# alte_schaltung_nicer.net
KiCad netlist of a schematic drawn in EAGLE
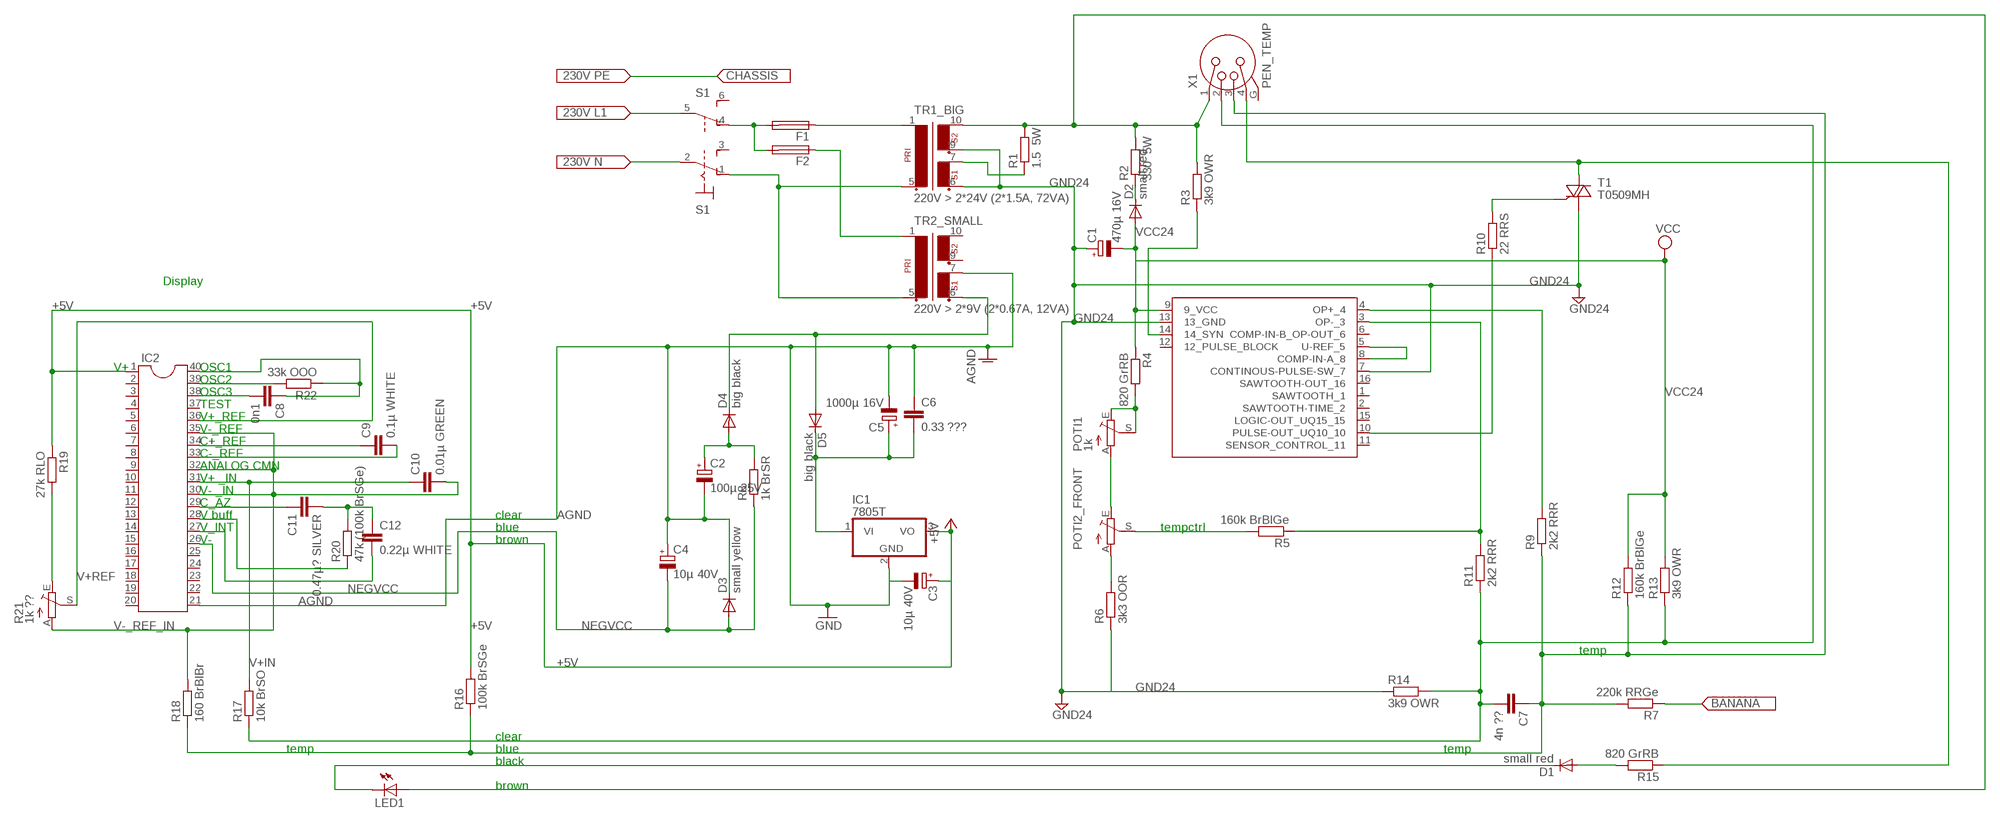
[diagram p0: schematic, sheet 1]

(export (version "E")
  (design (tool "Eeschema 10.0.6"))
  (components
    (comp (ref "C1")
      (value "470µ 16V")
      (footprint "eagle-import:E5-10,5")
      (libsource (lib "eagle-import") (part "CPOL-EUE5-10.5"))
    )
    (comp (ref "C2")
      (value "100µ 25V")
      (footprint "eagle-import:E5-10,5")
      (libsource (lib "eagle-import") (part "CPOL-EUE5-10.5"))
    )
    (comp (ref "C3")
      (value "10µ 40V")
      (footprint "eagle-import:E5-10,5")
      (libsource (lib "eagle-import") (part "CPOL-EUE5-10.5"))
    )
    (comp (ref "C4")
      (value "10µ 40V")
      (footprint "eagle-import:E5-10,5")
      (libsource (lib "eagle-import") (part "CPOL-EUE5-10.5"))
    )
    (comp (ref "C5")
      (value "1000µ 16V")
      (footprint "eagle-import:E5-10,5")
      (libsource (lib "eagle-import") (part "CPOL-EUE5-10.5"))
    )
    (comp (ref "C6")
      (value "0.33 ???")
      (footprint "eagle-import:C075-042X103")
      (libsource (lib "eagle-import") (part "C-EU075-042X103"))
    )
    (comp (ref "C7")
      (value "4n ??")
      (footprint "eagle-import:C050-024X044")
      (libsource (lib "eagle-import") (part "C-EU050-024X044"))
    )
    (comp (ref "C8")
      (value "0n1")
      (footprint "eagle-import:C050-024X044")
      (libsource (lib "eagle-import") (part "C-EU050-024X044"))
    )
    (comp (ref "C9")
      (value "0.1µ WHITE")
      (footprint "eagle-import:C102-043X133")
      (libsource (lib "eagle-import") (part "C-EU102-043X133"))
    )
    (comp (ref "C10")
      (value "0.01µ GREEN")
      (footprint "eagle-import:C102-043X133")
      (libsource (lib "eagle-import") (part "C-EU102-043X133"))
    )
    (comp (ref "C11")
      (value "0.47µ? SILVER")
      (footprint "eagle-import:C102-043X133")
      (libsource (lib "eagle-import") (part "C-EU102-043X133"))
    )
    (comp (ref "C12")
      (value "0.22µ WHITE")
      (footprint "eagle-import:C102-043X133")
      (libsource (lib "eagle-import") (part "C-EU102-043X133"))
    )
    (comp (ref "D1")
      (value "small red")
      (footprint "eagle-import:DO41-10")
      (libsource (lib "eagle-import") (part "1N4004"))
    )
    (comp (ref "D2")
      (value "small red")
      (footprint "eagle-import:DO41-10")
      (libsource (lib "eagle-import") (part "1N4004"))
    )
    (comp (ref "D3")
      (value "small yellow")
      (footprint "eagle-import:DO35-10")
      (libsource (lib "eagle-import") (part "1N4446"))
    )
    (comp (ref "D4")
      (value "big black")
      (footprint "eagle-import:DO41-10")
      (libsource (lib "eagle-import") (part "1N4942"))
    )
    (comp (ref "D5")
      (value "big black")
      (footprint "eagle-import:DO41-10")
      (libsource (lib "eagle-import") (part "1N4942"))
    )
    (comp (ref "F1")
      (value "SH25")
      (footprint "eagle-import:SH25")
      (fields (field (name "MF") "SCHURTER") (field (name "MPN") "0031.8211"))
      (libsource (lib "eagle-import") (part "SH25"))
    )
    (comp (ref "F2")
      (value "SH25")
      (footprint "eagle-import:SH25")
      (fields (field (name "MF") "SCHURTER") (field (name "MPN") "0031.8211"))
      (libsource (lib "eagle-import") (part "SH25"))
    )
    (comp (ref "IC1")
      (value "7805T")
      (footprint "eagle-import:TO220H")
      (libsource (lib "eagle-import") (part "78T05"))
    )
    (comp (ref "IC2")
      (value "DIL40")
      (footprint "eagle-import:DIL40")
      (libsource (lib "eagle-import") (part "DIL40"))
    )
    (comp (ref "LED1")
      (value "LED3MM")
      (footprint "eagle-import:LED3MM")
      (libsource (lib "eagle-import") (part "LED3MM"))
    )
    (comp (ref "POTI1")
      (value "1k")
      (footprint "eagle-import:LI10")
      (libsource (lib "eagle-import") (part "TRIM_EU-LI10"))
    )
    (comp (ref "POTI2_FRONT")
      (value "TRIM_EU-RJ9W")
      (footprint "eagle-import:RJ9W")
      (libsource (lib "eagle-import") (part "TRIM_EU-RJ9W"))
    )
    (comp (ref "R1")
      (value "1.5 5W")
      (footprint "eagle-import:0922_22")
      (libsource (lib "eagle-import") (part "R-EU_0922/22"))
    )
    (comp (ref "R2")
      (value "330 5W")
      (footprint "eagle-import:0922_22")
      (libsource (lib "eagle-import") (part "R-EU_0922/22"))
    )
    (comp (ref "R3")
      (value "3k9 OWR")
      (footprint "eagle-import:0207_12")
      (libsource (lib "eagle-import") (part "R-EU_0207/12"))
    )
    (comp (ref "R4")
      (value "820 GrRB")
      (footprint "eagle-import:0207_12")
      (libsource (lib "eagle-import") (part "R-EU_0207/12"))
    )
    (comp (ref "R5")
      (value "160k BrBlGe")
      (footprint "eagle-import:0207_12")
      (libsource (lib "eagle-import") (part "R-EU_0207/12"))
    )
    (comp (ref "R6")
      (value "3k3 OOR")
      (footprint "eagle-import:0207_12")
      (libsource (lib "eagle-import") (part "R-EU_0207/12"))
    )
    (comp (ref "R7")
      (value "220k RRGe")
      (footprint "eagle-import:0207_12")
      (libsource (lib "eagle-import") (part "R-EU_0207/12"))
    )
    (comp (ref "R8")
      (value "1k BrSR")
      (footprint "eagle-import:0207_12")
      (libsource (lib "eagle-import") (part "R-EU_0207/12"))
    )
    (comp (ref "R9")
      (value "2k2 RRR")
      (footprint "eagle-import:0207_12")
      (libsource (lib "eagle-import") (part "R-EU_0207/12"))
    )
    (comp (ref "R10")
      (value "22 RRS")
      (footprint "eagle-import:0207_12")
      (libsource (lib "eagle-import") (part "R-EU_0207/12"))
    )
    (comp (ref "R11")
      (value "2k2 RRR")
      (footprint "eagle-import:0207_12")
      (libsource (lib "eagle-import") (part "R-EU_0207/12"))
    )
    (comp (ref "R12")
      (value "160k BrBlGe")
      (footprint "eagle-import:0207_12")
      (libsource (lib "eagle-import") (part "R-EU_0207/12"))
    )
    (comp (ref "R13")
      (value "3k9 OWR")
      (footprint "eagle-import:0207_12")
      (libsource (lib "eagle-import") (part "R-EU_0207/12"))
    )
    (comp (ref "R14")
      (value "3k9 OWR")
      (footprint "eagle-import:0207_12")
      (libsource (lib "eagle-import") (part "R-EU_0207/12"))
    )
    (comp (ref "R15")
      (value "820 GrRB")
      (footprint "eagle-import:0207_12")
      (libsource (lib "eagle-import") (part "R-EU_0207/12"))
    )
    (comp (ref "R16")
      (value "100k BrSGe")
      (footprint "eagle-import:0207_12")
      (libsource (lib "eagle-import") (part "R-EU_0207/12"))
    )
    (comp (ref "R17")
      (value "10k BrSO")
      (footprint "eagle-import:0207_12")
      (libsource (lib "eagle-import") (part "R-EU_0207/12"))
    )
    (comp (ref "R18")
      (value "160 BrBlBr")
      (footprint "eagle-import:0207_12")
      (libsource (lib "eagle-import") (part "R-EU_0207/12"))
    )
    (comp (ref "R19")
      (value "27k RLO")
      (footprint "eagle-import:0207_12")
      (libsource (lib "eagle-import") (part "R-EU_0207/12"))
    )
    (comp (ref "R20")
      (value "47k (100k BrSGe)")
      (footprint "eagle-import:0207_12")
      (libsource (lib "eagle-import") (part "R-EU_0207/12"))
    )
    (comp (ref "R21")
      (value "1k ??")
      (footprint "eagle-import:SP19L")
      (libsource (lib "eagle-import") (part "TRIM_EU-B90P"))
    )
    (comp (ref "R22")
      (value "33k OOO")
      (footprint "eagle-import:0207_12")
      (libsource (lib "eagle-import") (part "R-EU_0207/12"))
    )
    (comp (ref "S1")
      (value "320-938")
      (footprint "eagle-import:320-938")
      (libsource (lib "eagle-import") (part "320-938"))
    )
    (comp (ref "T1")
      (value "T0509MH")
      (footprint "eagle-import:TO220AB")
      (libsource (lib "eagle-import") (part "BT136"))
    )
    (comp (ref "TR1_BIG")
      (value "220V > 2*24V (2*1.5A, 72VA)")
      (footprint "eagle-import:EI42-2")
      (libsource (lib "eagle-import") (part "EI42-2"))
    )
    (comp (ref "TR2_SMALL")
      (value "220V > 2*9V (2*0.67A, 12VA)")
      (footprint "eagle-import:EI42-2")
      (libsource (lib "eagle-import") (part "EI42-2"))
    )
    (comp (ref "U$1")
      (value "U106BS-DIL16")
      (footprint "eagle-import:DIL16")
      (libsource (lib "eagle-import") (part "U106BS-DIL16"))
    )
    (comp (ref "X1")
      (value "PEN_TEMP")
      (footprint "eagle-import:NC4FBV")
      (fields (field (name "MPN") "NC4FBV"))
      (libsource (lib "eagle-import") (part "NC4FBV"))
    )
  )
  (nets
    (net (code "1") (name "+5V") (class "Default")
      (node (ref "C3") (pin "+") (pinfunction "+_+") (pintype "passive"))
      (node (ref "IC1") (pin "3") (pinfunction "VO_3") (pintype "passive"))
      (node (ref "IC2") (pin "1") (pinfunction "1_1") (pintype "passive"))
      (node (ref "R16") (pin "2") (pinfunction "2_2") (pintype "passive"))
      (node (ref "R19") (pin "1") (pinfunction "1_1") (pintype "passive"))
    )
    (net (code "2") (name "/NEGVCC") (class "Default")
      (node (ref "C4") (pin "-") (pinfunction "-_-") (pintype "passive"))
      (node (ref "D3") (pin "A") (pinfunction "A_A") (pintype "passive"))
      (node (ref "IC2") (pin "26") (pinfunction "26_26") (pintype "passive"))
      (node (ref "R8") (pin "1") (pinfunction "1_1") (pintype "passive"))
    )
    (net (code "3") (name "/V+IN") (class "Default")
      (node (ref "C10") (pin "1") (pinfunction "1_1") (pintype "passive"))
      (node (ref "IC2") (pin "31") (pinfunction "31_31") (pintype "passive"))
      (node (ref "R17") (pin "2") (pinfunction "2_2") (pintype "passive"))
    )
    (net (code "4") (name "/V+REF") (class "Default")
      (node (ref "IC2") (pin "36") (pinfunction "36_36") (pintype "passive"))
      (node (ref "R21") (pin "S") (pinfunction "S_S") (pintype "passive"))
    )
    (net (code "5") (name "/V-_REF_IN") (class "Default")
      (node (ref "C10") (pin "2") (pinfunction "2_2") (pintype "passive"))
      (node (ref "IC2") (pin "30") (pinfunction "30_30") (pintype "passive"))
      (node (ref "IC2") (pin "32") (pinfunction "32_32") (pintype "passive"))
      (node (ref "IC2") (pin "35") (pinfunction "35_35") (pintype "passive"))
      (node (ref "R18") (pin "2") (pinfunction "2_2") (pintype "passive"))
      (node (ref "R21") (pin "A") (pinfunction "A_A") (pintype "passive"))
    )
    (net (code "6") (name "AGND") (class "Default")
      (node (ref "C2") (pin "-") (pinfunction "-_-") (pintype "passive"))
      (node (ref "C3") (pin "-") (pinfunction "-_-") (pintype "passive"))
      (node (ref "C4") (pin "+") (pinfunction "+_+") (pintype "passive"))
      (node (ref "C5") (pin "-") (pinfunction "-_-") (pintype "passive"))
      (node (ref "C6") (pin "1") (pinfunction "1_1") (pintype "passive"))
      (node (ref "D3") (pin "C") (pinfunction "C_C") (pintype "passive"))
      (node (ref "IC1") (pin "2") (pinfunction "GND_2") (pintype "passive"))
      (node (ref "IC2") (pin "21") (pinfunction "21_21") (pintype "passive"))
      (node (ref "TR2_SMALL") (pin "7") (pinfunction "4_7") (pintype "passive"))
    )
    (net (code "7") (name "GND24") (class "Default")
      (node (ref "C1") (pin "+") (pinfunction "+_+") (pintype "passive"))
      (node (ref "R14") (pin "1") (pinfunction "1_1") (pintype "passive"))
      (node (ref "R6") (pin "1") (pinfunction "1_1") (pintype "passive"))
      (node (ref "T1") (pin "1") (pinfunction "A1_1") (pintype "passive"))
      (node (ref "TR1_BIG") (pin "6") (pinfunction "3_6") (pintype "passive"))
      (node (ref "TR1_BIG") (pin "9") (pinfunction "5_9") (pintype "passive"))
      (node (ref "U$1") (pin "13") (pinfunction "13_GND_13") (pintype "power_in"))
      (node (ref "U$1") (pin "7") (pinfunction "CONTINOUS-PULSE-SW_7_7") (pintype "input"))
    )
    (net (code "8") (name "Net-(C2-Pad+)") (class "Default")
      (node (ref "C2") (pin "+") (pinfunction "+_+") (pintype "passive"))
      (node (ref "D4") (pin "A") (pinfunction "A_A") (pintype "passive"))
      (node (ref "R8") (pin "2") (pinfunction "2_2") (pintype "passive"))
    )
    (net (code "9") (name "Net-(C7-Pad1)") (class "Default")
      (node (ref "C7") (pin "1") (pinfunction "1_1") (pintype "passive"))
      (node (ref "R12") (pin "1") (pinfunction "1_1") (pintype "passive"))
      (node (ref "R16") (pin "1") (pinfunction "1_1") (pintype "passive"))
      (node (ref "R18") (pin "1") (pinfunction "1_1") (pintype "passive"))
      (node (ref "R7") (pin "2") (pinfunction "2_2") (pintype "passive"))
      (node (ref "R9") (pin "1") (pinfunction "1_1") (pintype "passive"))
      (node (ref "X1") (pin "3") (pinfunction "3_3") (pintype "passive"))
    )
    (net (code "10") (name "Net-(C7-Pad2)") (class "Default")
      (node (ref "C7") (pin "2") (pinfunction "2_2") (pintype "passive"))
      (node (ref "R11") (pin "1") (pinfunction "1_1") (pintype "passive"))
      (node (ref "R13") (pin "1") (pinfunction "1_1") (pintype "passive"))
      (node (ref "R14") (pin "2") (pinfunction "2_2") (pintype "passive"))
      (node (ref "R17") (pin "1") (pinfunction "1_1") (pintype "passive"))
      (node (ref "X1") (pin "2") (pinfunction "2_2") (pintype "passive"))
    )
    (net (code "11") (name "Net-(C8-Pad1)") (class "Default")
      (node (ref "C8") (pin "1") (pinfunction "1_1") (pintype "passive"))
      (node (ref "IC2") (pin "40") (pinfunction "40_40") (pintype "passive"))
      (node (ref "R22") (pin "1") (pinfunction "1_1") (pintype "passive"))
    )
    (net (code "12") (name "Net-(C8-Pad2)") (class "Default")
      (node (ref "C8") (pin "2") (pinfunction "2_2") (pintype "passive"))
      (node (ref "IC2") (pin "38") (pinfunction "38_38") (pintype "passive"))
    )
    (net (code "13") (name "Net-(C9-Pad1)") (class "Default")
      (node (ref "C9") (pin "1") (pinfunction "1_1") (pintype "passive"))
      (node (ref "IC2") (pin "34") (pinfunction "34_34") (pintype "passive"))
    )
    (net (code "14") (name "Net-(C9-Pad2)") (class "Default")
      (node (ref "C9") (pin "2") (pinfunction "2_2") (pintype "passive"))
      (node (ref "IC2") (pin "33") (pinfunction "33_33") (pintype "passive"))
    )
    (net (code "15") (name "Net-(C11-Pad1)") (class "Default")
      (node (ref "C11") (pin "1") (pinfunction "1_1") (pintype "passive"))
      (node (ref "IC2") (pin "29") (pinfunction "29_29") (pintype "passive"))
    )
    (net (code "16") (name "Net-(C11-Pad2)") (class "Default")
      (node (ref "C11") (pin "2") (pinfunction "2_2") (pintype "passive"))
      (node (ref "C12") (pin "1") (pinfunction "1_1") (pintype "passive"))
      (node (ref "R20") (pin "2") (pinfunction "2_2") (pintype "passive"))
    )
    (net (code "17") (name "Net-(C12-Pad2)") (class "Default")
      (node (ref "C12") (pin "2") (pinfunction "2_2") (pintype "passive"))
      (node (ref "IC2") (pin "27") (pinfunction "27_27") (pintype "passive"))
    )
    (net (code "18") (name "Net-(D1-PadA)") (class "Default")
      (node (ref "D1") (pin "A") (pinfunction "A_A") (pintype "passive"))
      (node (ref "R15") (pin "2") (pinfunction "2_2") (pintype "passive"))
    )
    (net (code "19") (name "Net-(D2-PadC)") (class "Default")
      (node (ref "D2") (pin "C") (pinfunction "C_C") (pintype "passive"))
      (node (ref "R2") (pin "1") (pinfunction "1_1") (pintype "passive"))
    )
    (net (code "20") (name "Net-(F1-Pad1)") (class "Default")
      (node (ref "F1") (pin "1") (pinfunction "1_1") (pintype "passive"))
      (node (ref "TR1_BIG") (pin "1") (pinfunction "1_1") (pintype "passive"))
    )
    (net (code "21") (name "Net-(F2-Pad1)") (class "Default")
      (node (ref "F2") (pin "1") (pinfunction "1_1") (pintype "passive"))
      (node (ref "TR2_SMALL") (pin "1") (pinfunction "1_1") (pintype "passive"))
    )
    (net (code "22") (name "Net-(IC1-VI)") (class "Default")
      (node (ref "C5") (pin "+") (pinfunction "+_+") (pintype "passive"))
      (node (ref "C6") (pin "2") (pinfunction "2_2") (pintype "passive"))
      (node (ref "D5") (pin "C") (pinfunction "C_C") (pintype "passive"))
      (node (ref "IC1") (pin "1") (pinfunction "VI_1") (pintype "input"))
    )
    (net (code "23") (name "Net-(IC2-Pad28)") (class "Default")
      (node (ref "IC2") (pin "28") (pinfunction "28_28") (pintype "passive"))
      (node (ref "R20") (pin "1") (pinfunction "1_1") (pintype "passive"))
    )
    (net (code "24") (name "Net-(IC2-Pad39)") (class "Default")
      (node (ref "IC2") (pin "39") (pinfunction "39_39") (pintype "passive"))
      (node (ref "R22") (pin "2") (pinfunction "2_2") (pintype "passive"))
    )
    (net (code "25") (name "Net-(LED1-C)") (class "Default")
      (node (ref "D1") (pin "C") (pinfunction "C_C") (pintype "passive"))
      (node (ref "LED1") (pin "K") (pinfunction "C_K") (pintype "passive"))
    )
    (net (code "26") (name "Net-(POTI1-PadA)") (class "Default")
      (node (ref "POTI1") (pin "A") (pinfunction "A_A") (pintype "passive"))
      (node (ref "POTI2_FRONT") (pin "E") (pinfunction "E_E") (pintype "passive"))
    )
    (net (code "27") (name "Net-(POTI1-PadE)") (class "Default")
      (node (ref "POTI1") (pin "E") (pinfunction "E_E") (pintype "passive"))
      (node (ref "POTI1") (pin "S") (pinfunction "S_S") (pintype "passive"))
      (node (ref "R4") (pin "2") (pinfunction "2_2") (pintype "passive"))
    )
    (net (code "28") (name "Net-(POTI2_FRONT-PadA)") (class "Default")
      (node (ref "POTI2_FRONT") (pin "A") (pinfunction "A_A") (pintype "passive"))
      (node (ref "R6") (pin "2") (pinfunction "2_2") (pintype "passive"))
    )
    (net (code "29") (name "Net-(POTI2_FRONT-PadS)") (class "Default")
      (node (ref "POTI2_FRONT") (pin "S") (pinfunction "S_S") (pintype "passive"))
      (node (ref "R5") (pin "2") (pinfunction "2_2") (pintype "passive"))
    )
    (net (code "30") (name "Net-(R19-Pad2)") (class "Default")
      (node (ref "R19") (pin "2") (pinfunction "2_2") (pintype "passive"))
      (node (ref "R21") (pin "E") (pinfunction "E_E") (pintype "passive"))
    )
    (net (code "31") (name "Net-(S1A-O)") (class "Default")
      (node (ref "S1") (pin "1") (pinfunction "O_1") (pintype "passive"))
      (node (ref "TR1_BIG") (pin "5") (pinfunction "2_5") (pintype "passive"))
      (node (ref "TR2_SMALL") (pin "5") (pinfunction "2_5") (pintype "passive"))
    )
    (net (code "32") (name "Net-(S1B-O)") (class "Default")
      (node (ref "F1") (pin "2") (pinfunction "2_2") (pintype "passive"))
      (node (ref "F2") (pin "2") (pinfunction "2_2") (pintype "passive"))
      (node (ref "S1") (pin "4") (pinfunction "O_4") (pintype "passive"))
    )
    (net (code "33") (name "Net-(T1-A2)") (class "Default")
      (node (ref "R15") (pin "1") (pinfunction "1_1") (pintype "passive"))
      (node (ref "T1") (pin "2") (pinfunction "A2_2") (pintype "passive"))
      (node (ref "X1") (pin "4") (pinfunction "4_4") (pintype "passive"))
    )
    (net (code "34") (name "Net-(T1-G)") (class "Default")
      (node (ref "R10") (pin "2") (pinfunction "2_2") (pintype "passive"))
      (node (ref "T1") (pin "3") (pinfunction "G_3") (pintype "passive"))
    )
    (net (code "35") (name "Net-(TR1_BIG-4)") (class "Default")
      (node (ref "R1") (pin "1") (pinfunction "1_1") (pintype "passive"))
      (node (ref "TR1_BIG") (pin "7") (pinfunction "4_7") (pintype "passive"))
    )
    (net (code "36") (name "Net-(TR1_BIG-6)") (class "Default")
      (node (ref "LED1") (pin "A") (pinfunction "A_A") (pintype "passive"))
      (node (ref "R1") (pin "2") (pinfunction "2_2") (pintype "passive"))
      (node (ref "R2") (pin "2") (pinfunction "2_2") (pintype "passive"))
      (node (ref "R3") (pin "2") (pinfunction "2_2") (pintype "passive"))
      (node (ref "TR1_BIG") (pin "10") (pinfunction "6_10") (pintype "passive"))
      (node (ref "X1") (pin "1") (pinfunction "1_1") (pintype "passive"))
    )
    (net (code "37") (name "Net-(TR2_SMALL-3)") (class "Default")
      (node (ref "D4") (pin "C") (pinfunction "C_C") (pintype "passive"))
      (node (ref "D5") (pin "A") (pinfunction "A_A") (pintype "passive"))
      (node (ref "TR2_SMALL") (pin "6") (pinfunction "3_6") (pintype "passive"))
    )
    (net (code "38") (name "Net-(U$1-14_SYN)") (class "Default")
      (node (ref "R3") (pin "1") (pinfunction "1_1") (pintype "passive"))
      (node (ref "U$1") (pin "14") (pinfunction "14_SYN_14") (pintype "input"))
    )
    (net (code "39") (name "Net-(U$1-COMP-IN-A_8)") (class "Default")
      (node (ref "U$1") (pin "5") (pinfunction "U-REF_5_5") (pintype "input"))
      (node (ref "U$1") (pin "8") (pinfunction "COMP-IN-A_8_8") (pintype "input"))
    )
    (net (code "40") (name "Net-(U$1-OP+_4)") (class "Default")
      (node (ref "R9") (pin "2") (pinfunction "2_2") (pintype "passive"))
      (node (ref "U$1") (pin "4") (pinfunction "OP+_4_4") (pintype "input"))
    )
    (net (code "41") (name "Net-(U$1-OP-_3)") (class "Default")
      (node (ref "R11") (pin "2") (pinfunction "2_2") (pintype "passive"))
      (node (ref "R5") (pin "1") (pinfunction "1_1") (pintype "passive"))
      (node (ref "U$1") (pin "3") (pinfunction "OP-_3_3") (pintype "input"))
    )
    (net (code "42") (name "Net-(U$1-PULSE-OUT_UQ10_10)") (class "Default")
      (node (ref "R10") (pin "1") (pinfunction "1_1") (pintype "passive"))
      (node (ref "U$1") (pin "10") (pinfunction "PULSE-OUT_UQ10_10_10") (pintype "output"))
    )
    (net (code "43") (name "VCC") (class "Default")
      (node (ref "C1") (pin "-") (pinfunction "-_-") (pintype "passive"))
      (node (ref "D2") (pin "A") (pinfunction "A_A") (pintype "passive"))
      (node (ref "R12") (pin "2") (pinfunction "2_2") (pintype "passive"))
      (node (ref "R13") (pin "2") (pinfunction "2_2") (pintype "passive"))
      (node (ref "R4") (pin "1") (pinfunction "1_1") (pintype "passive"))
      (node (ref "U$1") (pin "9") (pinfunction "9_VCC_9") (pintype "power_in"))
    )
    (net (code "44") (name "unconnected-(IC2-Pad2)") (class "Default")
      (node (ref "IC2") (pin "2") (pinfunction "2_2") (pintype "passive"))
    )
    (net (code "45") (name "unconnected-(IC2-Pad3)") (class "Default")
      (node (ref "IC2") (pin "3") (pinfunction "3_3") (pintype "passive"))
    )
    (net (code "46") (name "unconnected-(IC2-Pad4)") (class "Default")
      (node (ref "IC2") (pin "4") (pinfunction "4_4") (pintype "passive"))
    )
    (net (code "47") (name "unconnected-(IC2-Pad5)") (class "Default")
      (node (ref "IC2") (pin "5") (pinfunction "5_5") (pintype "passive"))
    )
    (net (code "48") (name "unconnected-(IC2-Pad6)") (class "Default")
      (node (ref "IC2") (pin "6") (pinfunction "6_6") (pintype "passive"))
    )
    (net (code "49") (name "unconnected-(IC2-Pad7)") (class "Default")
      (node (ref "IC2") (pin "7") (pinfunction "7_7") (pintype "passive"))
    )
    (net (code "50") (name "unconnected-(IC2-Pad8)") (class "Default")
      (node (ref "IC2") (pin "8") (pinfunction "8_8") (pintype "passive"))
    )
    (net (code "51") (name "unconnected-(IC2-Pad9)") (class "Default")
      (node (ref "IC2") (pin "9") (pinfunction "9_9") (pintype "passive"))
    )
    (net (code "52") (name "unconnected-(IC2-Pad10)") (class "Default")
      (node (ref "IC2") (pin "10") (pinfunction "10_10") (pintype "passive"))
    )
    (net (code "53") (name "unconnected-(IC2-Pad11)") (class "Default")
      (node (ref "IC2") (pin "11") (pinfunction "11_11") (pintype "passive"))
    )
    (net (code "54") (name "unconnected-(IC2-Pad12)") (class "Default")
      (node (ref "IC2") (pin "12") (pinfunction "12_12") (pintype "passive"))
    )
    (net (code "55") (name "unconnected-(IC2-Pad13)") (class "Default")
      (node (ref "IC2") (pin "13") (pinfunction "13_13") (pintype "passive"))
    )
    (net (code "56") (name "unconnected-(IC2-Pad14)") (class "Default")
      (node (ref "IC2") (pin "14") (pinfunction "14_14") (pintype "passive"))
    )
    (net (code "57") (name "unconnected-(IC2-Pad15)") (class "Default")
      (node (ref "IC2") (pin "15") (pinfunction "15_15") (pintype "passive"))
    )
    (net (code "58") (name "unconnected-(IC2-Pad16)") (class "Default")
      (node (ref "IC2") (pin "16") (pinfunction "16_16") (pintype "passive"))
    )
    (net (code "59") (name "unconnected-(IC2-Pad17)") (class "Default")
      (node (ref "IC2") (pin "17") (pinfunction "17_17") (pintype "passive"))
    )
    (net (code "60") (name "unconnected-(IC2-Pad18)") (class "Default")
      (node (ref "IC2") (pin "18") (pinfunction "18_18") (pintype "passive"))
    )
    (net (code "61") (name "unconnected-(IC2-Pad19)") (class "Default")
      (node (ref "IC2") (pin "19") (pinfunction "19_19") (pintype "passive"))
    )
    (net (code "62") (name "unconnected-(IC2-Pad20)") (class "Default")
      (node (ref "IC2") (pin "20") (pinfunction "20_20") (pintype "passive"))
    )
    (net (code "63") (name "unconnected-(IC2-Pad22)") (class "Default")
      (node (ref "IC2") (pin "22") (pinfunction "22_22") (pintype "passive"))
    )
    (net (code "64") (name "unconnected-(IC2-Pad23)") (class "Default")
      (node (ref "IC2") (pin "23") (pinfunction "23_23") (pintype "passive"))
    )
    (net (code "65") (name "unconnected-(IC2-Pad24)") (class "Default")
      (node (ref "IC2") (pin "24") (pinfunction "24_24") (pintype "passive"))
    )
    (net (code "66") (name "unconnected-(IC2-Pad25)") (class "Default")
      (node (ref "IC2") (pin "25") (pinfunction "25_25") (pintype "passive"))
    )
    (net (code "67") (name "unconnected-(IC2-Pad37)") (class "Default")
      (node (ref "IC2") (pin "37") (pinfunction "37_37") (pintype "passive"))
    )
    (net (code "68") (name "unconnected-(R7-Pad1)") (class "Default")
      (node (ref "R7") (pin "1") (pinfunction "1_1") (pintype "passive"))
    )
    (net (code "69") (name "unconnected-(S1A-P-Pad2)") (class "Default")
      (node (ref "S1") (pin "2") (pinfunction "P_2") (pintype "passive"))
    )
    (net (code "70") (name "unconnected-(S1A-S-Pad3)") (class "Default")
      (node (ref "S1") (pin "3") (pinfunction "S_3") (pintype "passive"))
    )
    (net (code "71") (name "unconnected-(S1B-P-Pad5)") (class "Default")
      (node (ref "S1") (pin "5") (pinfunction "P_5") (pintype "passive"))
    )
    (net (code "72") (name "unconnected-(S1B-S-Pad6)") (class "Default")
      (node (ref "S1") (pin "6") (pinfunction "S_6") (pintype "passive"))
    )
    (net (code "73") (name "unconnected-(TR2_SMALL-5-Pad9)") (class "Default")
      (node (ref "TR2_SMALL") (pin "9") (pinfunction "5_9") (pintype "passive"))
    )
    (net (code "74") (name "unconnected-(TR2_SMALL-6-Pad10)") (class "Default")
      (node (ref "TR2_SMALL") (pin "10") (pinfunction "6_10") (pintype "passive"))
    )
    (net (code "75") (name "unconnected-(U$1-12_PULSE_BLOCK-Pad12)") (class "Default")
      (node (ref "U$1") (pin "12") (pinfunction "12_PULSE_BLOCK_12") (pintype "input"))
    )
    (net (code "76") (name "unconnected-(U$1-COMP-IN-B_OP-OUT_6-Pad6)") (class "Default")
      (node (ref "U$1") (pin "6") (pinfunction "COMP-IN-B_OP-OUT_6_6") (pintype "output"))
    )
    (net (code "77") (name "unconnected-(U$1-LOGIC-OUT_UQ15_15-Pad15)") (class "Default")
      (node (ref "U$1") (pin "15") (pinfunction "LOGIC-OUT_UQ15_15_15") (pintype "output"))
    )
    (net (code "78") (name "unconnected-(U$1-SAWTOOTH-OUT_16-Pad16)") (class "Default")
      (node (ref "U$1") (pin "16") (pinfunction "SAWTOOTH-OUT_16_16") (pintype "output"))
    )
    (net (code "79") (name "unconnected-(U$1-SAWTOOTH-TIME_2-Pad2)") (class "Default")
      (node (ref "U$1") (pin "2") (pinfunction "SAWTOOTH-TIME_2_2") (pintype "input"))
    )
    (net (code "80") (name "unconnected-(U$1-SAWTOOTH_1-Pad1)") (class "Default")
      (node (ref "U$1") (pin "1") (pinfunction "SAWTOOTH_1_1") (pintype "input"))
    )
    (net (code "81") (name "unconnected-(U$1-SENSOR_CONTROL_11-Pad11)") (class "Default")
      (node (ref "U$1") (pin "11") (pinfunction "SENSOR_CONTROL_11_11") (pintype "input"))
    )
    (net (code "82") (name "unconnected-(X1-PadG)") (class "Default")
      (node (ref "X1") (pin "G") (pinfunction "G_G") (pintype "passive"))
    )
  )
)
